# SoftCore_SA_P2_PG2.net
KiCad netlist of a schematic drawn in Altium Designer
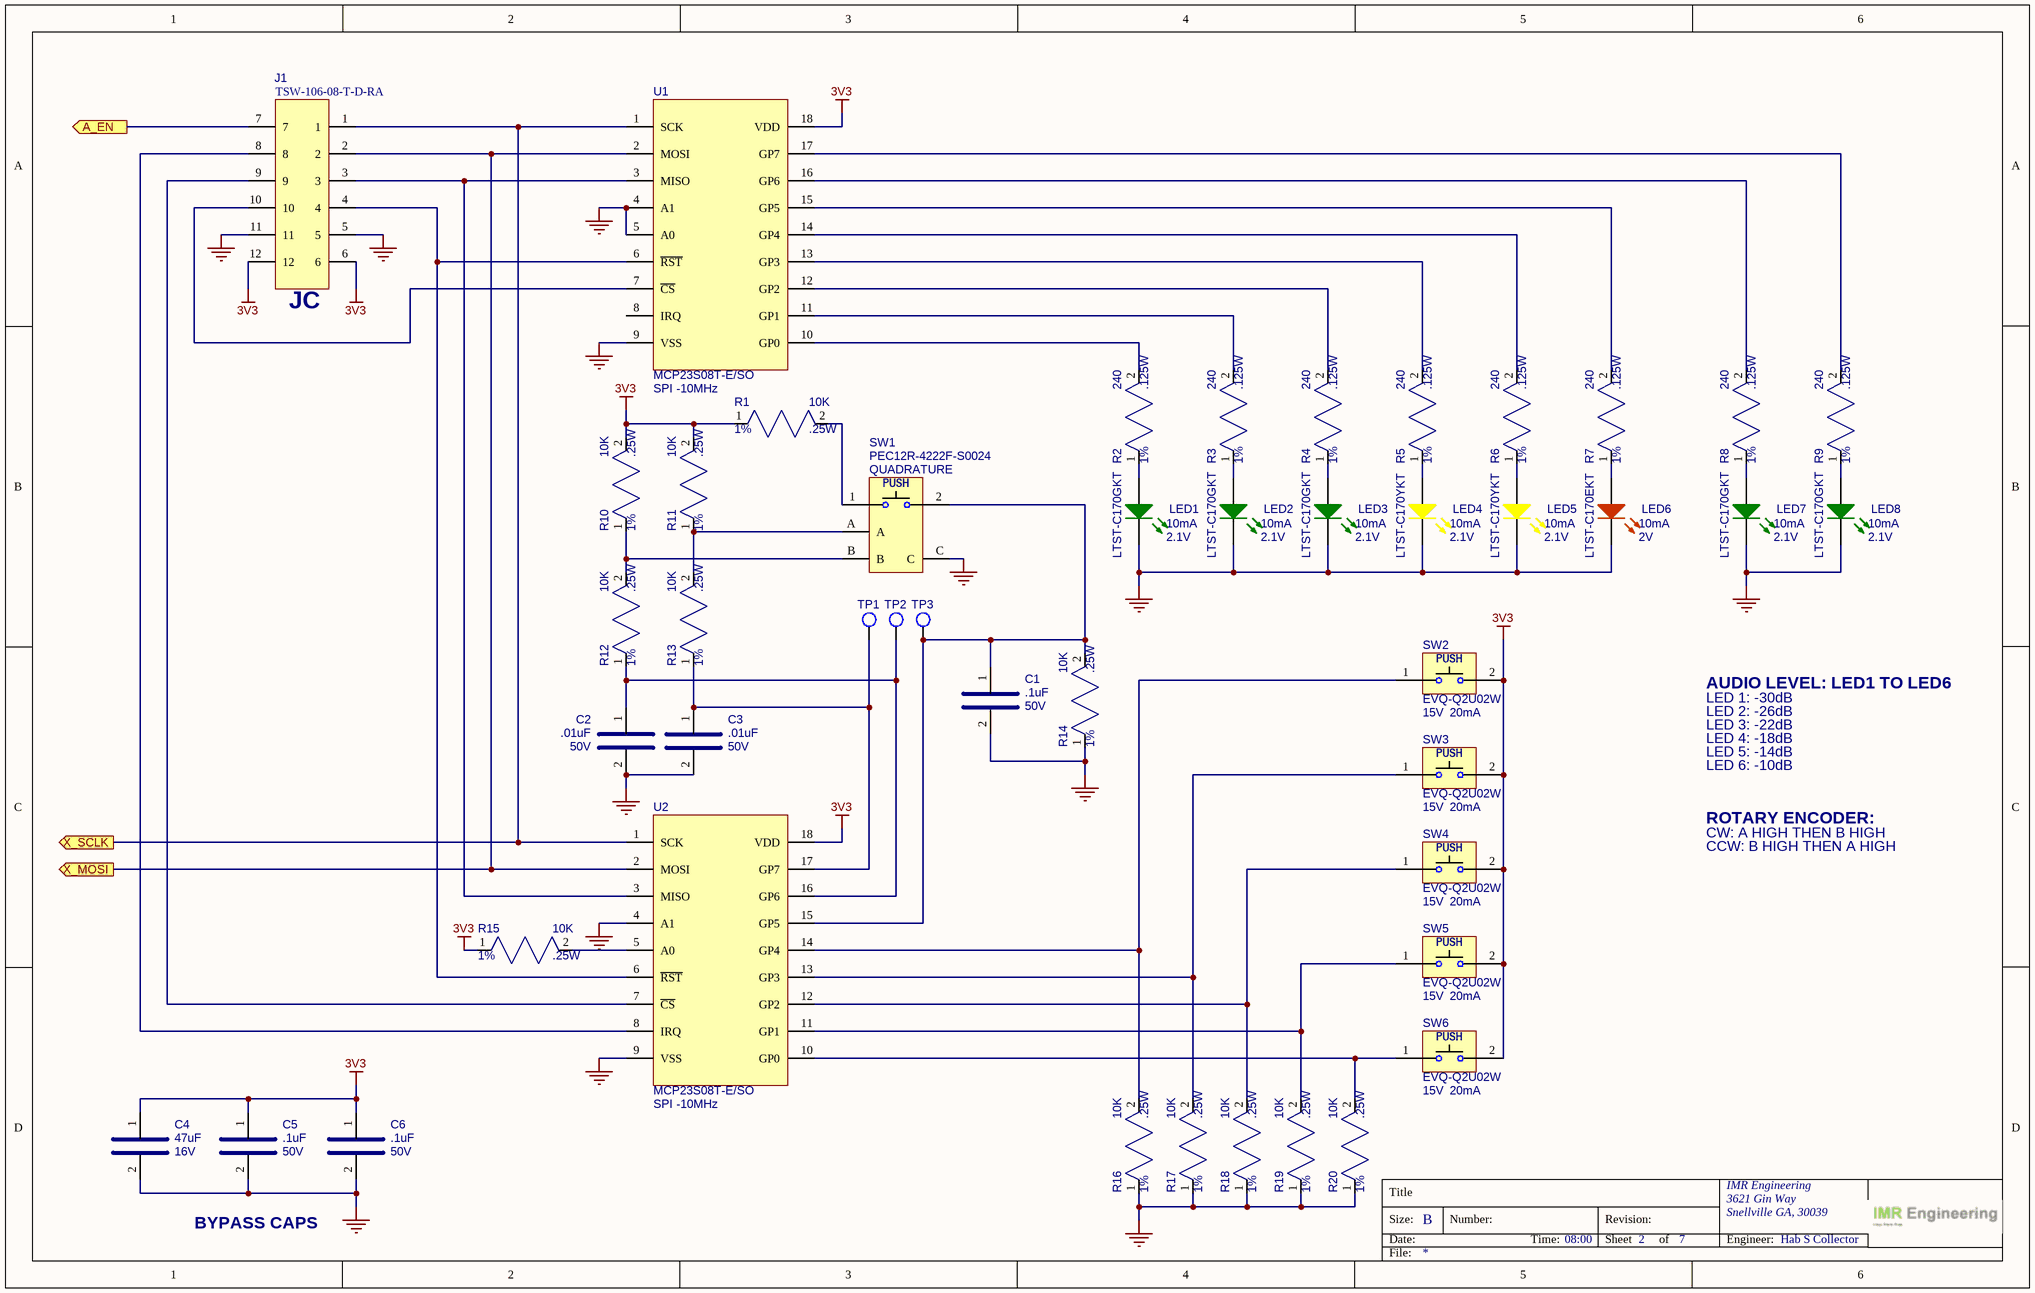
[diagram p0: SoftCore_SA_P2_PG2.SchDoc]

(export (version "E")
  (design (tool "Eeschema 10.0.6"))
  (components
    (comp (ref "C1")
      (value ".1uF")
      (footprint "CAP_0805")
      (description "CAP CER 0.1UF 50V X7R 0805")
      (fields
        (field (name "MFG") "KYOCERA AVX")
        (field (name "VOLTAGE") "50V")
        (field (name "Comment") "KGM21NR71H104KT")
      )
      (libsource (lib "IMR_LIB_SCH_R2") (part "CAP_SMD_0.1UF_50V_0805"))
    )
    (comp (ref "C2")
      (value ".01uF")
      (footprint "CAP_0805")
      (description "CAP CER 0.01UF 50V X7R 0805")
      (fields
        (field (name "MFG") "KYOCERA AVX")
        (field (name "VOLTAGE") "50V")
        (field (name "Comment") "KGM21NR71H103KT")
      )
      (libsource (lib "IMR_LIB_SCH_R2") (part "CAP_SMD_0.01UF_50V_0805"))
    )
    (comp (ref "C3")
      (value ".01uF")
      (footprint "CAP_0805")
      (description "CAP CER 0.01UF 50V X7R 0805")
      (fields
        (field (name "MFG") "KYOCERA AVX")
        (field (name "VOLTAGE") "50V")
        (field (name "Comment") "KGM21NR71H103KT")
      )
      (libsource (lib "IMR_LIB_SCH_R2") (part "CAP_SMD_0.01UF_50V_0805"))
    )
    (comp (ref "C4")
      (value "47uF")
      (footprint "CAP_1210")
      (description "CAP CER 47UF 50V X5R 1210")
      (fields
        (field (name "MFG") "Murata Electronics")
        (field (name "VOLTAGE") "16V")
        (field (name "Comment") "GRM32ER60J476ME20L")
      )
      (libsource (lib "IMR_LIB_SCH_R2") (part "CAP_SMD_47UF_16V_1210"))
    )
    (comp (ref "C5")
      (value ".1uF")
      (footprint "CAP_0805")
      (description "CAP CER 0.1UF 50V X7R 0805")
      (fields
        (field (name "MFG") "KYOCERA AVX")
        (field (name "VOLTAGE") "50V")
        (field (name "Comment") "KGM21NR71H104KT")
      )
      (libsource (lib "IMR_LIB_SCH_R2") (part "CAP_SMD_0.1UF_50V_0805"))
    )
    (comp (ref "C6")
      (value ".1uF")
      (footprint "CAP_0805")
      (description "CAP CER 0.1UF 50V X7R 0805")
      (fields
        (field (name "MFG") "KYOCERA AVX")
        (field (name "VOLTAGE") "50V")
        (field (name "Comment") "KGM21NR71H104KT")
      )
      (libsource (lib "IMR_LIB_SCH_R2") (part "CAP_SMD_0.1UF_50V_0805"))
    )
    (comp (ref "J1")
      (value "TSW-106-08-T-D-RA")
      (footprint "SAMTEC_TSW-106-08-T-D-RA")
      (description "CONN HEADER R/A 12POS 2.54MM")
      (fields (field (name "MFG") "Samtec Inc.") (field (name "MFG_PN") "TSW-106-08-T-D-RA"))
      (libsource (lib "IMR_LIB_SCH_R2") (part "CONN_HEADER_12P_100MIL_RA"))
    )
    (comp (ref "LED1")
      (value "2.1V")
      (footprint "LED_0805")
      (description "LED GREEN CLEAR SMD")
      (fields
        (field (name "MFG") "Lite-On")
        (field (name "MFG_PN") "LTST-C170GKT")
        (field (name "CURRENT") "10mA")
        (field (name "Comment") "LTST-C170GKT")
      )
      (libsource (lib "IMR_LIB_SCH_R2") (part "LED_GREEN_LTST-C170GKT"))
    )
    (comp (ref "LED2")
      (value "2.1V")
      (footprint "LED_0805")
      (description "LED GREEN CLEAR SMD")
      (fields
        (field (name "MFG") "Lite-On")
        (field (name "MFG_PN") "LTST-C170GKT")
        (field (name "CURRENT") "10mA")
        (field (name "Comment") "LTST-C170GKT")
      )
      (libsource (lib "IMR_LIB_SCH_R2") (part "LED_GREEN_LTST-C170GKT"))
    )
    (comp (ref "LED3")
      (value "2.1V")
      (footprint "LED_0805")
      (description "LED GREEN CLEAR SMD")
      (fields
        (field (name "MFG") "Lite-On")
        (field (name "MFG_PN") "LTST-C170GKT")
        (field (name "CURRENT") "10mA")
        (field (name "Comment") "LTST-C170GKT")
      )
      (libsource (lib "IMR_LIB_SCH_R2") (part "LED_GREEN_LTST-C170GKT"))
    )
    (comp (ref "LED4")
      (value "2.1V")
      (footprint "LED_0805")
      (description "LED YELLOW CLEAR SMD")
      (fields
        (field (name "MFG") "Lite-On")
        (field (name "MFG_PN") "LTST-C170YKT")
        (field (name "CURRENT") "10mA")
        (field (name "Comment") "LTST-C170YKT")
      )
      (libsource (lib "IMR_LIB_SCH_R2") (part "LED_YELLOW_LTST-C170YKT"))
    )
    (comp (ref "LED5")
      (value "2.1V")
      (footprint "LED_0805")
      (description "LED YELLOW CLEAR SMD")
      (fields
        (field (name "MFG") "Lite-On")
        (field (name "MFG_PN") "LTST-C170YKT")
        (field (name "CURRENT") "10mA")
        (field (name "Comment") "LTST-C170YKT")
      )
      (libsource (lib "IMR_LIB_SCH_R2") (part "LED_YELLOW_LTST-C170YKT"))
    )
    (comp (ref "LED6")
      (value "2V")
      (footprint "LED_0805")
      (description "LED RED CLEAR SMD")
      (fields
        (field (name "MFG") "Lite-On")
        (field (name "MFG_PN") "LTST-C170EKT")
        (field (name "CURRENT") "10mA")
        (field (name "Comment") "LTST-C170EKT")
      )
      (libsource (lib "IMR_LIB_SCH_R2") (part "LED_RED_LTST-C170EKT"))
    )
    (comp (ref "LED7")
      (value "2.1V")
      (footprint "LED_0805")
      (description "LED GREEN CLEAR SMD")
      (fields
        (field (name "MFG") "Lite-On")
        (field (name "MFG_PN") "LTST-C170GKT")
        (field (name "CURRENT") "10mA")
        (field (name "Comment") "LTST-C170GKT")
      )
      (libsource (lib "IMR_LIB_SCH_R2") (part "LED_GREEN_LTST-C170GKT"))
    )
    (comp (ref "LED8")
      (value "2.1V")
      (footprint "LED_0805")
      (description "LED GREEN CLEAR SMD")
      (fields
        (field (name "MFG") "Lite-On")
        (field (name "MFG_PN") "LTST-C170GKT")
        (field (name "CURRENT") "10mA")
        (field (name "Comment") "LTST-C170GKT")
      )
      (libsource (lib "IMR_LIB_SCH_R2") (part "LED_GREEN_LTST-C170GKT"))
    )
    (comp (ref "R1")
      (value "10K")
      (footprint "RES_0805")
      (description "RES SMD 10K OHM 1% 1/4W 0805")
      (fields
        (field (name "MFG") "Yageo")
        (field (name "POWER") ".25W")
        (field (name "TOLERANCE") "1%")
        (field (name "Comment") "RC0805FR-7W10KL")
      )
      (libsource (lib "IMR_LIB_SCH_R2") (part "RES_SMD_10K_0805_1/4W_1%"))
    )
    (comp (ref "R2")
      (value "240")
      (footprint "RES_0805")
      (description "RES SMD 240 OHM 1% 1/8W 0805")
      (fields
        (field (name "MFG") "Yageo")
        (field (name "POWER") ".125W")
        (field (name "TOLERANCE") "1%")
        (field (name "Comment") "RC0805FR-13240RL")
      )
      (libsource (lib "IMR_LIB_SCH_R2") (part "RES_SMD_240_0805_1/8W_1%"))
    )
    (comp (ref "R3")
      (value "240")
      (footprint "RES_0805")
      (description "RES SMD 240 OHM 1% 1/8W 0805")
      (fields
        (field (name "MFG") "Yageo")
        (field (name "POWER") ".125W")
        (field (name "TOLERANCE") "1%")
        (field (name "Comment") "RC0805FR-13240RL")
      )
      (libsource (lib "IMR_LIB_SCH_R2") (part "RES_SMD_240_0805_1/8W_1%"))
    )
    (comp (ref "R4")
      (value "240")
      (footprint "RES_0805")
      (description "RES SMD 240 OHM 1% 1/8W 0805")
      (fields
        (field (name "MFG") "Yageo")
        (field (name "POWER") ".125W")
        (field (name "TOLERANCE") "1%")
        (field (name "Comment") "RC0805FR-13240RL")
      )
      (libsource (lib "IMR_LIB_SCH_R2") (part "RES_SMD_240_0805_1/8W_1%"))
    )
    (comp (ref "R5")
      (value "240")
      (footprint "RES_0805")
      (description "RES SMD 240 OHM 1% 1/8W 0805")
      (fields
        (field (name "MFG") "Yageo")
        (field (name "POWER") ".125W")
        (field (name "TOLERANCE") "1%")
        (field (name "Comment") "RC0805FR-13240RL")
      )
      (libsource (lib "IMR_LIB_SCH_R2") (part "RES_SMD_240_0805_1/8W_1%"))
    )
    (comp (ref "R6")
      (value "240")
      (footprint "RES_0805")
      (description "RES SMD 240 OHM 1% 1/8W 0805")
      (fields
        (field (name "MFG") "Yageo")
        (field (name "POWER") ".125W")
        (field (name "TOLERANCE") "1%")
        (field (name "Comment") "RC0805FR-13240RL")
      )
      (libsource (lib "IMR_LIB_SCH_R2") (part "RES_SMD_240_0805_1/8W_1%"))
    )
    (comp (ref "R7")
      (value "240")
      (footprint "RES_0805")
      (description "RES SMD 240 OHM 1% 1/8W 0805")
      (fields
        (field (name "MFG") "Yageo")
        (field (name "POWER") ".125W")
        (field (name "TOLERANCE") "1%")
        (field (name "Comment") "RC0805FR-13240RL")
      )
      (libsource (lib "IMR_LIB_SCH_R2") (part "RES_SMD_240_0805_1/8W_1%"))
    )
    (comp (ref "R8")
      (value "240")
      (footprint "RES_0805")
      (description "RES SMD 240 OHM 1% 1/8W 0805")
      (fields
        (field (name "MFG") "Yageo")
        (field (name "POWER") ".125W")
        (field (name "TOLERANCE") "1%")
        (field (name "Comment") "RC0805FR-13240RL")
      )
      (libsource (lib "IMR_LIB_SCH_R2") (part "RES_SMD_240_0805_1/8W_1%"))
    )
    (comp (ref "R9")
      (value "240")
      (footprint "RES_0805")
      (description "RES SMD 240 OHM 1% 1/8W 0805")
      (fields
        (field (name "MFG") "Yageo")
        (field (name "POWER") ".125W")
        (field (name "TOLERANCE") "1%")
        (field (name "Comment") "RC0805FR-13240RL")
      )
      (libsource (lib "IMR_LIB_SCH_R2") (part "RES_SMD_240_0805_1/8W_1%"))
    )
    (comp (ref "R10")
      (value "10K")
      (footprint "RES_0805")
      (description "RES SMD 10K OHM 1% 1/4W 0805")
      (fields
        (field (name "MFG") "Yageo")
        (field (name "POWER") ".25W")
        (field (name "TOLERANCE") "1%")
        (field (name "Comment") "RC0805FR-7W10KL")
      )
      (libsource (lib "IMR_LIB_SCH_R2") (part "RES_SMD_10K_0805_1/4W_1%"))
    )
    (comp (ref "R11")
      (value "10K")
      (footprint "RES_0805")
      (description "RES SMD 10K OHM 1% 1/4W 0805")
      (fields
        (field (name "MFG") "Yageo")
        (field (name "POWER") ".25W")
        (field (name "TOLERANCE") "1%")
        (field (name "Comment") "RC0805FR-7W10KL")
      )
      (libsource (lib "IMR_LIB_SCH_R2") (part "RES_SMD_10K_0805_1/4W_1%"))
    )
    (comp (ref "R12")
      (value "10K")
      (footprint "RES_0805")
      (description "RES SMD 10K OHM 1% 1/4W 0805")
      (fields
        (field (name "MFG") "Yageo")
        (field (name "POWER") ".25W")
        (field (name "TOLERANCE") "1%")
        (field (name "Comment") "RC0805FR-7W10KL")
      )
      (libsource (lib "IMR_LIB_SCH_R2") (part "RES_SMD_10K_0805_1/4W_1%"))
    )
    (comp (ref "R13")
      (value "10K")
      (footprint "RES_0805")
      (description "RES SMD 10K OHM 1% 1/4W 0805")
      (fields
        (field (name "MFG") "Yageo")
        (field (name "POWER") ".25W")
        (field (name "TOLERANCE") "1%")
        (field (name "Comment") "RC0805FR-7W10KL")
      )
      (libsource (lib "IMR_LIB_SCH_R2") (part "RES_SMD_10K_0805_1/4W_1%"))
    )
    (comp (ref "R14")
      (value "10K")
      (footprint "RES_0805")
      (description "RES SMD 10K OHM 1% 1/4W 0805")
      (fields
        (field (name "MFG") "Yageo")
        (field (name "POWER") ".25W")
        (field (name "TOLERANCE") "1%")
        (field (name "Comment") "RC0805FR-7W10KL")
      )
      (libsource (lib "IMR_LIB_SCH_R2") (part "RES_SMD_10K_0805_1/4W_1%"))
    )
    (comp (ref "R15")
      (value "10K")
      (footprint "RES_0805")
      (description "RES SMD 10K OHM 1% 1/4W 0805")
      (fields
        (field (name "MFG") "Yageo")
        (field (name "POWER") ".25W")
        (field (name "TOLERANCE") "1%")
        (field (name "Comment") "RC0805FR-7W10KL")
      )
      (libsource (lib "IMR_LIB_SCH_R2") (part "RES_SMD_10K_0805_1/4W_1%"))
    )
    (comp (ref "R16")
      (value "10K")
      (footprint "RES_0805")
      (description "RES SMD 10K OHM 1% 1/4W 0805")
      (fields
        (field (name "MFG") "Yageo")
        (field (name "POWER") ".25W")
        (field (name "TOLERANCE") "1%")
        (field (name "Comment") "RC0805FR-7W10KL")
      )
      (libsource (lib "IMR_LIB_SCH_R2") (part "RES_SMD_10K_0805_1/4W_1%"))
    )
    (comp (ref "R17")
      (value "10K")
      (footprint "RES_0805")
      (description "RES SMD 10K OHM 1% 1/4W 0805")
      (fields
        (field (name "MFG") "Yageo")
        (field (name "POWER") ".25W")
        (field (name "TOLERANCE") "1%")
        (field (name "Comment") "RC0805FR-7W10KL")
      )
      (libsource (lib "IMR_LIB_SCH_R2") (part "RES_SMD_10K_0805_1/4W_1%"))
    )
    (comp (ref "R18")
      (value "10K")
      (footprint "RES_0805")
      (description "RES SMD 10K OHM 1% 1/4W 0805")
      (fields
        (field (name "MFG") "Yageo")
        (field (name "POWER") ".25W")
        (field (name "TOLERANCE") "1%")
        (field (name "Comment") "RC0805FR-7W10KL")
      )
      (libsource (lib "IMR_LIB_SCH_R2") (part "RES_SMD_10K_0805_1/4W_1%"))
    )
    (comp (ref "R19")
      (value "10K")
      (footprint "RES_0805")
      (description "RES SMD 10K OHM 1% 1/4W 0805")
      (fields
        (field (name "MFG") "Yageo")
        (field (name "POWER") ".25W")
        (field (name "TOLERANCE") "1%")
        (field (name "Comment") "RC0805FR-7W10KL")
      )
      (libsource (lib "IMR_LIB_SCH_R2") (part "RES_SMD_10K_0805_1/4W_1%"))
    )
    (comp (ref "R20")
      (value "10K")
      (footprint "RES_0805")
      (description "RES SMD 10K OHM 1% 1/4W 0805")
      (fields
        (field (name "MFG") "Yageo")
        (field (name "POWER") ".25W")
        (field (name "TOLERANCE") "1%")
        (field (name "Comment") "RC0805FR-7W10KL")
      )
      (libsource (lib "IMR_LIB_SCH_R2") (part "RES_SMD_10K_0805_1/4W_1%"))
    )
    (comp (ref "SW1")
      (value "PEC12R-4222F-S0024")
      (footprint "PEC12R-4222F-S0024")
      (description "ENCODER INCRE QUAD HORIZN PC PIN")
      (fields
        (field (name "MFG") "Bourns")
        (field (name "MFG_PN") "PEC12R-4222F-S0024")
        (field (name "OUTPUT") "QUADRATURE")
      )
      (libsource (lib "IMR_LIB_SCH_R2") (part "SWITCH_PEC12R-4222F-S0024"))
    )
    (comp (ref "SW2")
      (value "15V")
      (footprint "PANASONIC_EVQ-Q2U02W")
      (description "SWITCH TACTILE SPST-NO 0.02A 15V")
      (fields
        (field (name "MFG") "American Zettler")
        (field (name "MFG_PN") "EVQ-Q2U02W")
        (field (name "CURRENT") "20mA")
        (field (name "Comment") "EVQ-Q2U02W")
      )
      (libsource (lib "IMR_LIB_SCH_R2") (part "SWITCH_EVQ-Q2U02W"))
    )
    (comp (ref "SW3")
      (value "15V")
      (footprint "PANASONIC_EVQ-Q2U02W")
      (description "SWITCH TACTILE SPST-NO 0.02A 15V")
      (fields
        (field (name "MFG") "American Zettler")
        (field (name "MFG_PN") "EVQ-Q2U02W")
        (field (name "CURRENT") "20mA")
        (field (name "Comment") "EVQ-Q2U02W")
      )
      (libsource (lib "IMR_LIB_SCH_R2") (part "SWITCH_EVQ-Q2U02W"))
    )
    (comp (ref "SW4")
      (value "15V")
      (footprint "PANASONIC_EVQ-Q2U02W")
      (description "SWITCH TACTILE SPST-NO 0.02A 15V")
      (fields
        (field (name "MFG") "American Zettler")
        (field (name "MFG_PN") "EVQ-Q2U02W")
        (field (name "CURRENT") "20mA")
        (field (name "Comment") "EVQ-Q2U02W")
      )
      (libsource (lib "IMR_LIB_SCH_R2") (part "SWITCH_EVQ-Q2U02W"))
    )
    (comp (ref "SW5")
      (value "15V")
      (footprint "PANASONIC_EVQ-Q2U02W")
      (description "SWITCH TACTILE SPST-NO 0.02A 15V")
      (fields
        (field (name "MFG") "American Zettler")
        (field (name "MFG_PN") "EVQ-Q2U02W")
        (field (name "CURRENT") "20mA")
        (field (name "Comment") "EVQ-Q2U02W")
      )
      (libsource (lib "IMR_LIB_SCH_R2") (part "SWITCH_EVQ-Q2U02W"))
    )
    (comp (ref "SW6")
      (value "15V")
      (footprint "PANASONIC_EVQ-Q2U02W")
      (description "SWITCH TACTILE SPST-NO 0.02A 15V")
      (fields
        (field (name "MFG") "American Zettler")
        (field (name "MFG_PN") "EVQ-Q2U02W")
        (field (name "CURRENT") "20mA")
        (field (name "Comment") "EVQ-Q2U02W")
      )
      (libsource (lib "IMR_LIB_SCH_R2") (part "SWITCH_EVQ-Q2U02W"))
    )
    (comp (ref "TP1")
      (value "~")
      (footprint "TEST_POINT_35MIL_TH")
      (description "TEST POINT TH FITS DSO PROBE TIP")
      (libsource (lib "IMR_LIB_SCH_R2") (part "CONN_TEST_POINT_TH_PROBE_TIP"))
    )
    (comp (ref "TP2")
      (value "~")
      (footprint "TEST_POINT_35MIL_TH")
      (description "TEST POINT TH FITS DSO PROBE TIP")
      (libsource (lib "IMR_LIB_SCH_R2") (part "CONN_TEST_POINT_TH_PROBE_TIP"))
    )
    (comp (ref "TP3")
      (value "~")
      (footprint "TEST_POINT_35MIL_TH")
      (description "TEST POINT TH FITS DSO PROBE TIP")
      (libsource (lib "IMR_LIB_SCH_R2") (part "CONN_TEST_POINT_TH_PROBE_TIP"))
    )
    (comp (ref "U1")
      (value "SPI -10MHz")
      (footprint "SOIC-18_300")
      (description "IC IO XPNDR 10MHZ SPI 18SOIC")
      (fields
        (field (name "MFG") "Microchip")
        (field (name "MFG_PN") "MCP23S08T-E/SO")
        (field (name "Comment") "MCP23S08T-E/SO")
      )
      (libsource (lib "IMR_LIB_SCH_R2") (part "IC_MCP23S08T-E/SO"))
    )
    (comp (ref "U2")
      (value "SPI -10MHz")
      (footprint "SOIC-18_300")
      (description "IC IO XPNDR 10MHZ SPI 18SOIC")
      (fields
        (field (name "MFG") "Microchip")
        (field (name "MFG_PN") "MCP23S08T-E/SO")
        (field (name "Comment") "MCP23S08T-E/SO")
      )
      (libsource (lib "IMR_LIB_SCH_R2") (part "IC_MCP23S08T-E/SO"))
    )
  )
  (nets
    (net (code "1") (name "/A_EN") (class "Default")
      (node (ref "J1") (pin "7") (pinfunction "7_7") (pintype "passive"))
    )
    (net (code "2") (name "/X_MOSI") (class "Default")
      (node (ref "J1") (pin "2") (pinfunction "2_2") (pintype "passive"))
      (node (ref "U1") (pin "2") (pinfunction "MOSI_2") (pintype "passive"))
      (node (ref "U2") (pin "2") (pinfunction "MOSI_2") (pintype "passive"))
    )
    (net (code "3") (name "/X_SCLK") (class "Default")
      (node (ref "J1") (pin "1") (pinfunction "1_1") (pintype "passive"))
      (node (ref "U1") (pin "1") (pinfunction "SCK_1") (pintype "passive"))
      (node (ref "U2") (pin "1") (pinfunction "SCK_1") (pintype "passive"))
    )
    (net (code "4") (name "3V3") (class "Default")
      (node (ref "C4") (pin "1") (pinfunction "1_1") (pintype "passive"))
      (node (ref "C5") (pin "1") (pinfunction "1_1") (pintype "passive"))
      (node (ref "C6") (pin "1") (pinfunction "1_1") (pintype "passive"))
      (node (ref "J1") (pin "12") (pinfunction "12_12") (pintype "passive"))
      (node (ref "J1") (pin "6") (pinfunction "6_6") (pintype "passive"))
      (node (ref "R1") (pin "1") (pinfunction "1_1") (pintype "passive"))
      (node (ref "R10") (pin "2") (pinfunction "2_2") (pintype "passive"))
      (node (ref "R11") (pin "2") (pinfunction "2_2") (pintype "passive"))
      (node (ref "R15") (pin "1") (pinfunction "1_1") (pintype "passive"))
      (node (ref "SW2") (pin "2") (pinfunction "B'_2") (pintype "passive"))
      (node (ref "SW3") (pin "2") (pinfunction "B'_2") (pintype "passive"))
      (node (ref "SW4") (pin "2") (pinfunction "B'_2") (pintype "passive"))
      (node (ref "SW5") (pin "2") (pinfunction "B'_2") (pintype "passive"))
      (node (ref "SW6") (pin "2") (pinfunction "B'_2") (pintype "passive"))
      (node (ref "U1") (pin "18") (pinfunction "VDD_18") (pintype "passive"))
      (node (ref "U2") (pin "18") (pinfunction "VDD_18") (pintype "passive"))
    )
    (net (code "5") (name "GND") (class "Default")
      (node (ref "C1") (pin "2") (pinfunction "2_2") (pintype "passive"))
      (node (ref "C2") (pin "2") (pinfunction "2_2") (pintype "passive"))
      (node (ref "C3") (pin "2") (pinfunction "2_2") (pintype "passive"))
      (node (ref "C4") (pin "2") (pinfunction "2_2") (pintype "passive"))
      (node (ref "C5") (pin "2") (pinfunction "2_2") (pintype "passive"))
      (node (ref "C6") (pin "2") (pinfunction "2_2") (pintype "passive"))
      (node (ref "J1") (pin "11") (pinfunction "11_11") (pintype "passive"))
      (node (ref "J1") (pin "5") (pinfunction "5_5") (pintype "passive"))
      (node (ref "LED1") (pin "K") (pinfunction "K_K") (pintype "passive"))
      (node (ref "LED2") (pin "K") (pinfunction "K_K") (pintype "passive"))
      (node (ref "LED3") (pin "K") (pinfunction "K_K") (pintype "passive"))
      (node (ref "LED4") (pin "K") (pinfunction "K_K") (pintype "passive"))
      (node (ref "LED5") (pin "K") (pinfunction "K_K") (pintype "passive"))
      (node (ref "LED6") (pin "K") (pinfunction "K_K") (pintype "passive"))
      (node (ref "LED7") (pin "K") (pinfunction "K_K") (pintype "passive"))
      (node (ref "LED8") (pin "K") (pinfunction "K_K") (pintype "passive"))
      (node (ref "R14") (pin "1") (pinfunction "1_1") (pintype "passive"))
      (node (ref "R16") (pin "1") (pinfunction "1_1") (pintype "passive"))
      (node (ref "R17") (pin "1") (pinfunction "1_1") (pintype "passive"))
      (node (ref "R18") (pin "1") (pinfunction "1_1") (pintype "passive"))
      (node (ref "R19") (pin "1") (pinfunction "1_1") (pintype "passive"))
      (node (ref "R20") (pin "1") (pinfunction "1_1") (pintype "passive"))
      (node (ref "SW1") (pin "C") (pinfunction "C_C") (pintype "passive"))
      (node (ref "U1") (pin "4") (pinfunction "A1_4") (pintype "passive"))
      (node (ref "U1") (pin "5") (pinfunction "A0_5") (pintype "passive"))
      (node (ref "U1") (pin "9") (pinfunction "VSS_9") (pintype "passive"))
      (node (ref "U2") (pin "4") (pinfunction "A1_4") (pintype "passive"))
      (node (ref "U2") (pin "9") (pinfunction "VSS_9") (pintype "passive"))
    )
    (net (code "6") (name "Net-(LED1-PadA)") (class "Default")
      (node (ref "LED1") (pin "A") (pinfunction "A_A") (pintype "passive"))
      (node (ref "R2") (pin "1") (pinfunction "1_1") (pintype "passive"))
    )
    (net (code "7") (name "Net-(LED2-PadA)") (class "Default")
      (node (ref "LED2") (pin "A") (pinfunction "A_A") (pintype "passive"))
      (node (ref "R3") (pin "1") (pinfunction "1_1") (pintype "passive"))
    )
    (net (code "8") (name "Net-(LED3-PadA)") (class "Default")
      (node (ref "LED3") (pin "A") (pinfunction "A_A") (pintype "passive"))
      (node (ref "R4") (pin "1") (pinfunction "1_1") (pintype "passive"))
    )
    (net (code "9") (name "Net-(LED4-PadA)") (class "Default")
      (node (ref "LED4") (pin "A") (pinfunction "A_A") (pintype "passive"))
      (node (ref "R5") (pin "1") (pinfunction "1_1") (pintype "passive"))
    )
    (net (code "10") (name "Net-(LED5-PadA)") (class "Default")
      (node (ref "LED5") (pin "A") (pinfunction "A_A") (pintype "passive"))
      (node (ref "R6") (pin "1") (pinfunction "1_1") (pintype "passive"))
    )
    (net (code "11") (name "Net-(LED6-PadA)") (class "Default")
      (node (ref "LED6") (pin "A") (pinfunction "A_A") (pintype "passive"))
      (node (ref "R7") (pin "1") (pinfunction "1_1") (pintype "passive"))
    )
    (net (code "12") (name "Net-(LED7-PadA)") (class "Default")
      (node (ref "LED7") (pin "A") (pinfunction "A_A") (pintype "passive"))
      (node (ref "R8") (pin "1") (pinfunction "1_1") (pintype "passive"))
    )
    (net (code "13") (name "Net-(LED8-PadA)") (class "Default")
      (node (ref "LED8") (pin "A") (pinfunction "A_A") (pintype "passive"))
      (node (ref "R9") (pin "1") (pinfunction "1_1") (pintype "passive"))
    )
    (net (code "14") (name "Net-(R1-Pad2)") (class "Default")
      (node (ref "R1") (pin "2") (pinfunction "2_2") (pintype "passive"))
      (node (ref "SW1") (pin "1") (pinfunction "B_1") (pintype "passive"))
    )
    (net (code "15") (name "Net-(R10-Pad1)") (class "Default")
      (node (ref "R10") (pin "1") (pinfunction "1_1") (pintype "passive"))
      (node (ref "R12") (pin "2") (pinfunction "2_2") (pintype "passive"))
      (node (ref "SW1") (pin "B") (pinfunction "B_B") (pintype "passive"))
    )
    (net (code "16") (name "Net-(R11-Pad1)") (class "Default")
      (node (ref "R11") (pin "1") (pinfunction "1_1") (pintype "passive"))
      (node (ref "R13") (pin "2") (pinfunction "2_2") (pintype "passive"))
      (node (ref "SW1") (pin "A") (pinfunction "A_A") (pintype "passive"))
    )
    (net (code "17") (name "Net-(SW1-B')") (class "Default")
      (node (ref "C1") (pin "1") (pinfunction "1_1") (pintype "passive"))
      (node (ref "R14") (pin "2") (pinfunction "2_2") (pintype "passive"))
      (node (ref "SW1") (pin "2") (pinfunction "B'_2") (pintype "passive"))
      (node (ref "TP3") (pin "1") (pintype "passive"))
      (node (ref "U2") (pin "15") (pinfunction "GP5_15") (pintype "passive"))
    )
    (net (code "18") (name "Net-(SW2-B)") (class "Default")
      (node (ref "R16") (pin "2") (pinfunction "2_2") (pintype "passive"))
      (node (ref "SW2") (pin "1") (pinfunction "B_1") (pintype "passive"))
      (node (ref "U2") (pin "14") (pinfunction "GP4_14") (pintype "passive"))
    )
    (net (code "19") (name "Net-(SW3-B)") (class "Default")
      (node (ref "R17") (pin "2") (pinfunction "2_2") (pintype "passive"))
      (node (ref "SW3") (pin "1") (pinfunction "B_1") (pintype "passive"))
      (node (ref "U2") (pin "13") (pinfunction "GP3_13") (pintype "passive"))
    )
    (net (code "20") (name "Net-(SW4-B)") (class "Default")
      (node (ref "R18") (pin "2") (pinfunction "2_2") (pintype "passive"))
      (node (ref "SW4") (pin "1") (pinfunction "B_1") (pintype "passive"))
      (node (ref "U2") (pin "12") (pinfunction "GP2_12") (pintype "passive"))
    )
    (net (code "21") (name "Net-(SW5-B)") (class "Default")
      (node (ref "R19") (pin "2") (pinfunction "2_2") (pintype "passive"))
      (node (ref "SW5") (pin "1") (pinfunction "B_1") (pintype "passive"))
      (node (ref "U2") (pin "11") (pinfunction "GP1_11") (pintype "passive"))
    )
    (net (code "22") (name "Net-(SW6-B)") (class "Default")
      (node (ref "R20") (pin "2") (pinfunction "2_2") (pintype "passive"))
      (node (ref "SW6") (pin "1") (pinfunction "B_1") (pintype "passive"))
      (node (ref "U2") (pin "10") (pinfunction "GP0_10") (pintype "passive"))
    )
    (net (code "23") (name "Net-(U1-GP0)") (class "Default")
      (node (ref "R2") (pin "2") (pinfunction "2_2") (pintype "passive"))
      (node (ref "U1") (pin "10") (pinfunction "GP0_10") (pintype "passive"))
    )
    (net (code "24") (name "Net-(U1-GP1)") (class "Default")
      (node (ref "R3") (pin "2") (pinfunction "2_2") (pintype "passive"))
      (node (ref "U1") (pin "11") (pinfunction "GP1_11") (pintype "passive"))
    )
    (net (code "25") (name "Net-(U1-GP2)") (class "Default")
      (node (ref "R4") (pin "2") (pinfunction "2_2") (pintype "passive"))
      (node (ref "U1") (pin "12") (pinfunction "GP2_12") (pintype "passive"))
    )
    (net (code "26") (name "Net-(U1-GP3)") (class "Default")
      (node (ref "R5") (pin "2") (pinfunction "2_2") (pintype "passive"))
      (node (ref "U1") (pin "13") (pinfunction "GP3_13") (pintype "passive"))
    )
    (net (code "27") (name "Net-(U1-GP4)") (class "Default")
      (node (ref "R6") (pin "2") (pinfunction "2_2") (pintype "passive"))
      (node (ref "U1") (pin "14") (pinfunction "GP4_14") (pintype "passive"))
    )
    (net (code "28") (name "Net-(U1-GP5)") (class "Default")
      (node (ref "R7") (pin "2") (pinfunction "2_2") (pintype "passive"))
      (node (ref "U1") (pin "15") (pinfunction "GP5_15") (pintype "passive"))
    )
    (net (code "29") (name "Net-(U1-GP6)") (class "Default")
      (node (ref "R8") (pin "2") (pinfunction "2_2") (pintype "passive"))
      (node (ref "U1") (pin "16") (pinfunction "GP6_16") (pintype "passive"))
    )
    (net (code "30") (name "Net-(U1-GP7)") (class "Default")
      (node (ref "R9") (pin "2") (pinfunction "2_2") (pintype "passive"))
      (node (ref "U1") (pin "17") (pinfunction "GP7_17") (pintype "passive"))
    )
    (net (code "31") (name "Net-(U1-MISO)") (class "Default")
      (node (ref "J1") (pin "3") (pinfunction "3_3") (pintype "passive"))
      (node (ref "U1") (pin "3") (pinfunction "MISO_3") (pintype "passive"))
      (node (ref "U2") (pin "3") (pinfunction "MISO_3") (pintype "passive"))
    )
    (net (code "32") (name "Net-(U1-~{CS})") (class "Default")
      (node (ref "J1") (pin "10") (pinfunction "10_10") (pintype "passive"))
      (node (ref "U1") (pin "7") (pinfunction "~{CS}_7") (pintype "passive"))
    )
    (net (code "33") (name "Net-(U1-~{RST})") (class "Default")
      (node (ref "J1") (pin "4") (pinfunction "4_4") (pintype "passive"))
      (node (ref "U1") (pin "6") (pinfunction "~{RST}_6") (pintype "passive"))
      (node (ref "U2") (pin "6") (pinfunction "~{RST}_6") (pintype "passive"))
    )
    (net (code "34") (name "Net-(U2-A0)") (class "Default")
      (node (ref "R15") (pin "2") (pinfunction "2_2") (pintype "passive"))
      (node (ref "U2") (pin "5") (pinfunction "A0_5") (pintype "passive"))
    )
    (net (code "35") (name "Net-(U2-GP6)") (class "Default")
      (node (ref "C2") (pin "1") (pinfunction "1_1") (pintype "passive"))
      (node (ref "R12") (pin "1") (pinfunction "1_1") (pintype "passive"))
      (node (ref "TP2") (pin "1") (pintype "passive"))
      (node (ref "U2") (pin "16") (pinfunction "GP6_16") (pintype "passive"))
    )
    (net (code "36") (name "Net-(U2-GP7)") (class "Default")
      (node (ref "C3") (pin "1") (pinfunction "1_1") (pintype "passive"))
      (node (ref "R13") (pin "1") (pinfunction "1_1") (pintype "passive"))
      (node (ref "TP1") (pin "1") (pintype "passive"))
      (node (ref "U2") (pin "17") (pinfunction "GP7_17") (pintype "passive"))
    )
    (net (code "37") (name "Net-(U2-IRQ)") (class "Default")
      (node (ref "J1") (pin "8") (pinfunction "8_8") (pintype "passive"))
      (node (ref "U2") (pin "8") (pinfunction "IRQ_8") (pintype "passive"))
    )
    (net (code "38") (name "Net-(U2-~{CS})") (class "Default")
      (node (ref "J1") (pin "9") (pinfunction "9_9") (pintype "passive"))
      (node (ref "U2") (pin "7") (pinfunction "~{CS}_7") (pintype "passive"))
    )
    (net (code "39") (name "unconnected-(U1-IRQ-Pad8)") (class "Default")
      (node (ref "U1") (pin "8") (pinfunction "IRQ_8") (pintype "passive"))
    )
  )
)
